# LOADS.net
KiCad netlist of a schematic drawn in Altium Designer
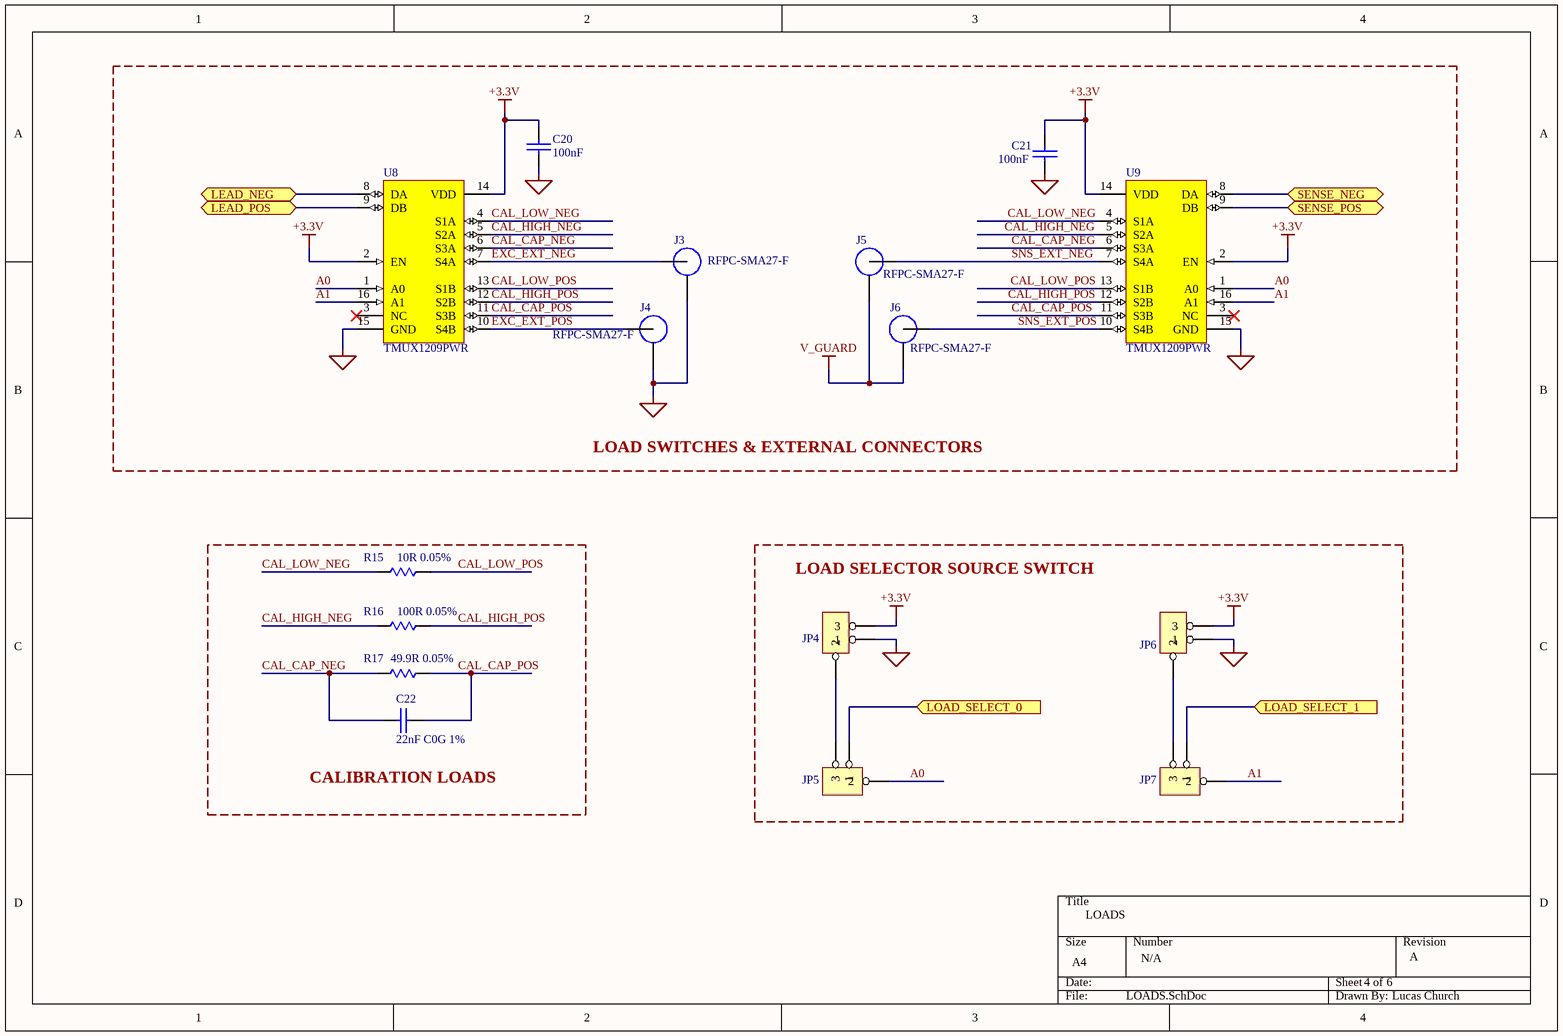
[diagram p0: LOADS.SchDoc]

(export (version "E")
  (design (tool "Eeschema 10.0.6"))
  (components
    (comp (ref "C20")
      (value "100nF")
      (footprint "0603-CAP")
      (description "CAP CER 100 NF 50V X7R 0603")
      (libsource (lib "SGL_Capacitors") (part "Capacitor"))
    )
    (comp (ref "C21")
      (value "100nF")
      (footprint "0603-CAP")
      (description "CAP CER 100 NF 50V X7R 0603")
      (libsource (lib "SGL_Capacitors") (part "Capacitor"))
    )
    (comp (ref "C22")
      (value "22nF C0G 1%")
      (footprint "0805-CAP")
      (description "CAP CER 0.022UF 50V C0G/NP0 0805")
      (libsource (lib "SGL_Capacitors") (part "Capacitor"))
    )
    (comp (ref "J3")
      (value "RFPC-SMA27-F")
      (footprint "GRADCONN_RFPC-SMA27-F")
      (fields (field (name "MF") "{'manufacturer': u'GCT (Gradconn)'}"))
      (libsource (lib "BioZ") (part "RFPC-SMA27-F"))
    )
    (comp (ref "J4")
      (value "RFPC-SMA27-F")
      (footprint "GRADCONN_RFPC-SMA27-F")
      (fields (field (name "MF") "{'manufacturer': u'GCT (Gradconn)'}"))
      (libsource (lib "BioZ") (part "RFPC-SMA27-F"))
    )
    (comp (ref "J5")
      (value "RFPC-SMA27-F")
      (footprint "GRADCONN_RFPC-SMA27-F")
      (fields (field (name "MF") "{'manufacturer': u'GCT (Gradconn)'}"))
      (libsource (lib "BioZ") (part "RFPC-SMA27-F"))
    )
    (comp (ref "J6")
      (value "RFPC-SMA27-F")
      (footprint "GRADCONN_RFPC-SMA27-F")
      (fields (field (name "MF") "{'manufacturer': u'GCT (Gradconn)'}"))
      (libsource (lib "BioZ") (part "RFPC-SMA27-F"))
    )
    (comp (ref "JP4")
      (value "JUMPER1X3")
      (footprint "JUMPER3")
      (description "CONN HEADER VERT 36POS 2.54MM")
      (libsource (lib "") (part "JUMPER1X3_1"))
    )
    (comp (ref "JP5")
      (value "JUMPER1X3")
      (footprint "JUMPER3")
      (description "CONN HEADER VERT 36POS 2.54MM")
      (libsource (lib "SGL_Connectors") (part "JUMPER1X3"))
    )
    (comp (ref "JP6")
      (value "JUMPER1X3")
      (footprint "JUMPER3")
      (description "CONN HEADER VERT 36POS 2.54MM")
      (libsource (lib "") (part "JUMPER1X3_1"))
    )
    (comp (ref "JP7")
      (value "JUMPER1X3")
      (footprint "JUMPER3")
      (description "CONN HEADER VERT 36POS 2.54MM")
      (libsource (lib "SGL_Connectors") (part "JUMPER1X3"))
    )
    (comp (ref "R15")
      (value "10R 0.05%")
      (footprint "0603-RES")
      (description "RES SMD 10OHM 0.05% 1/10W 0603")
      (libsource (lib "SGL_Resistives") (part "RESISTOR"))
    )
    (comp (ref "R16")
      (value "100R 0.05%")
      (footprint "0603-RES")
      (description "RES SMD 100OHM 0.05% 1/10W 0603")
      (libsource (lib "SGL_Resistives") (part "RESISTOR"))
    )
    (comp (ref "R17")
      (value "49.9R 0.05%")
      (footprint "0603-RES")
      (description "RES SMD 49.9OHM 0.05% 1/10W 0603")
      (libsource (lib "SGL_Resistives") (part "RESISTOR"))
    )
    (comp (ref "U8")
      (value "TMUX1209PWR")
      (footprint "PW0016A_N")
      (description "5-V, 4:1, 2-channel general-purpose multiplexer with 1.8-V input logic control 16-TSSOP -40 to 125")
      (fields (field (name "COPYRIGHT") "Copyright (C) 2025 Ultra Librarian. All rights reserved."))
      (libsource (lib "BioZ") (part "TMUX1209PWR"))
    )
    (comp (ref "U9")
      (value "TMUX1209PWR")
      (footprint "PW0016A_N")
      (description "5-V, 4:1, 2-channel general-purpose multiplexer with 1.8-V input logic control 16-TSSOP -40 to 125")
      (fields (field (name "COPYRIGHT") "Copyright (C) 2025 Ultra Librarian. All rights reserved."))
      (libsource (lib "") (part "TMUX1209PWR_1"))
    )
  )
  (nets
    (net (code "1") (name "+3.3V") (class "Default")
      (node (ref "C20") (pin "1") (pinfunction "1_1") (pintype "passive"))
      (node (ref "C21") (pin "1") (pinfunction "1_1") (pintype "passive"))
      (node (ref "JP4") (pin "3") (pinfunction "3_3") (pintype "passive"))
      (node (ref "JP6") (pin "3") (pinfunction "3_3") (pintype "passive"))
      (node (ref "U8") (pin "14") (pinfunction "VDD_14") (pintype "power_in"))
      (node (ref "U8") (pin "2") (pinfunction "EN_2") (pintype "input"))
      (node (ref "U9") (pin "14") (pinfunction "VDD_14") (pintype "power_in"))
      (node (ref "U9") (pin "2") (pinfunction "EN_2") (pintype "input"))
    )
    (net (code "2") (name "/A0") (class "Default")
      (node (ref "JP5") (pin "2") (pinfunction "2_2") (pintype "passive"))
      (node (ref "U8") (pin "1") (pinfunction "A0_1") (pintype "input"))
      (node (ref "U9") (pin "1") (pinfunction "A0_1") (pintype "input"))
    )
    (net (code "3") (name "/A1") (class "Default")
      (node (ref "JP7") (pin "2") (pinfunction "2_2") (pintype "passive"))
      (node (ref "U8") (pin "16") (pinfunction "A1_16") (pintype "input"))
      (node (ref "U9") (pin "16") (pinfunction "A1_16") (pintype "input"))
    )
    (net (code "4") (name "/CAL_CAP_NEG") (class "Default")
      (node (ref "C22") (pin "1") (pinfunction "1_1") (pintype "passive"))
      (node (ref "R17") (pin "1") (pinfunction "1_1") (pintype "passive"))
      (node (ref "U8") (pin "6") (pinfunction "S3A_6") (pintype "bidirectional"))
      (node (ref "U9") (pin "6") (pinfunction "S3A_6") (pintype "bidirectional"))
    )
    (net (code "5") (name "/CAL_CAP_POS") (class "Default")
      (node (ref "C22") (pin "2") (pinfunction "2_2") (pintype "passive"))
      (node (ref "R17") (pin "2") (pinfunction "2_2") (pintype "passive"))
      (node (ref "U8") (pin "11") (pinfunction "S3B_11") (pintype "bidirectional"))
      (node (ref "U9") (pin "11") (pinfunction "S3B_11") (pintype "bidirectional"))
    )
    (net (code "6") (name "/CAL_HIGH_NEG") (class "Default")
      (node (ref "R16") (pin "1") (pinfunction "1_1") (pintype "passive"))
      (node (ref "U8") (pin "5") (pinfunction "S2A_5") (pintype "bidirectional"))
      (node (ref "U9") (pin "5") (pinfunction "S2A_5") (pintype "bidirectional"))
    )
    (net (code "7") (name "/CAL_HIGH_POS") (class "Default")
      (node (ref "R16") (pin "2") (pinfunction "2_2") (pintype "passive"))
      (node (ref "U8") (pin "12") (pinfunction "S2B_12") (pintype "bidirectional"))
      (node (ref "U9") (pin "12") (pinfunction "S2B_12") (pintype "bidirectional"))
    )
    (net (code "8") (name "/CAL_LOW_NEG") (class "Default")
      (node (ref "R15") (pin "1") (pinfunction "1_1") (pintype "passive"))
      (node (ref "U8") (pin "4") (pinfunction "S1A_4") (pintype "bidirectional"))
      (node (ref "U9") (pin "4") (pinfunction "S1A_4") (pintype "bidirectional"))
    )
    (net (code "9") (name "/CAL_LOW_POS") (class "Default")
      (node (ref "R15") (pin "2") (pinfunction "2_2") (pintype "passive"))
      (node (ref "U8") (pin "13") (pinfunction "S1B_13") (pintype "bidirectional"))
      (node (ref "U9") (pin "13") (pinfunction "S1B_13") (pintype "bidirectional"))
    )
    (net (code "10") (name "/EXC_EXT_NEG") (class "Default")
      (node (ref "J3") (pin "SIG") (pinfunction "SIG_SIG") (pintype "passive"))
      (node (ref "U8") (pin "7") (pinfunction "S4A_7") (pintype "bidirectional"))
    )
    (net (code "11") (name "/EXC_EXT_POS") (class "Default")
      (node (ref "J4") (pin "SIG") (pinfunction "SIG_SIG") (pintype "passive"))
      (node (ref "U8") (pin "10") (pinfunction "S4B_10") (pintype "bidirectional"))
    )
    (net (code "12") (name "/LEAD_NEG") (class "Default")
      (node (ref "U8") (pin "8") (pinfunction "DA_8") (pintype "bidirectional"))
    )
    (net (code "13") (name "/LEAD_POS") (class "Default")
      (node (ref "U8") (pin "9") (pinfunction "DB_9") (pintype "bidirectional"))
    )
    (net (code "14") (name "/LOAD_SELECT_0") (class "Default")
      (node (ref "JP5") (pin "1") (pinfunction "1_1") (pintype "passive"))
    )
    (net (code "15") (name "/LOAD_SELECT_1") (class "Default")
      (node (ref "JP7") (pin "1") (pinfunction "1_1") (pintype "passive"))
    )
    (net (code "16") (name "/SENSE_NEG") (class "Default")
      (node (ref "U9") (pin "8") (pinfunction "DA_8") (pintype "bidirectional"))
    )
    (net (code "17") (name "/SENSE_POS") (class "Default")
      (node (ref "U9") (pin "9") (pinfunction "DB_9") (pintype "bidirectional"))
    )
    (net (code "18") (name "/SNS_EXT_NEG") (class "Default")
      (node (ref "J5") (pin "SIG") (pinfunction "SIG_SIG") (pintype "passive"))
      (node (ref "U9") (pin "7") (pinfunction "S4A_7") (pintype "bidirectional"))
    )
    (net (code "19") (name "/SNS_EXT_POS") (class "Default")
      (node (ref "J6") (pin "SIG") (pinfunction "SIG_SIG") (pintype "passive"))
      (node (ref "U9") (pin "10") (pinfunction "S4B_10") (pintype "bidirectional"))
    )
    (net (code "20") (name "GND") (class "Default")
      (node (ref "C20") (pin "2") (pinfunction "2_2") (pintype "passive"))
      (node (ref "C21") (pin "2") (pinfunction "2_2") (pintype "passive"))
      (node (ref "J3") (pin "SHLD") (pinfunction "SHLD_SHLD") (pintype "power_in"))
      (node (ref "J4") (pin "SHLD") (pinfunction "SHLD_SHLD") (pintype "power_in"))
      (node (ref "JP4") (pin "1") (pinfunction "1_1") (pintype "passive"))
      (node (ref "JP6") (pin "1") (pinfunction "1_1") (pintype "passive"))
      (node (ref "U8") (pin "15") (pinfunction "GND_15") (pintype "power_in"))
      (node (ref "U9") (pin "15") (pinfunction "GND_15") (pintype "power_in"))
    )
    (net (code "21") (name "Net-(JP4-Pad2)") (class "Default")
      (node (ref "JP4") (pin "2") (pinfunction "2_2") (pintype "passive"))
      (node (ref "JP5") (pin "3") (pinfunction "3_3") (pintype "passive"))
    )
    (net (code "22") (name "Net-(JP6-Pad2)") (class "Default")
      (node (ref "JP6") (pin "2") (pinfunction "2_2") (pintype "passive"))
      (node (ref "JP7") (pin "3") (pinfunction "3_3") (pintype "passive"))
    )
    (net (code "23") (name "V_GUARD") (class "Default")
      (node (ref "J5") (pin "SHLD") (pinfunction "SHLD_SHLD") (pintype "power_in"))
      (node (ref "J6") (pin "SHLD") (pinfunction "SHLD_SHLD") (pintype "power_in"))
    )
    (net (code "24") (name "unconnected-(U8-NC-Pad3)") (class "Default")
      (node (ref "U8") (pin "3") (pinfunction "NC_3") (pintype "passive+no_connect"))
    )
    (net (code "25") (name "unconnected-(U9-NC-Pad3)") (class "Default")
      (node (ref "U9") (pin "3") (pinfunction "NC_3") (pintype "passive+no_connect"))
    )
  )
)
